# W5500.net
KiCad netlist of a schematic drawn in Altium Designer
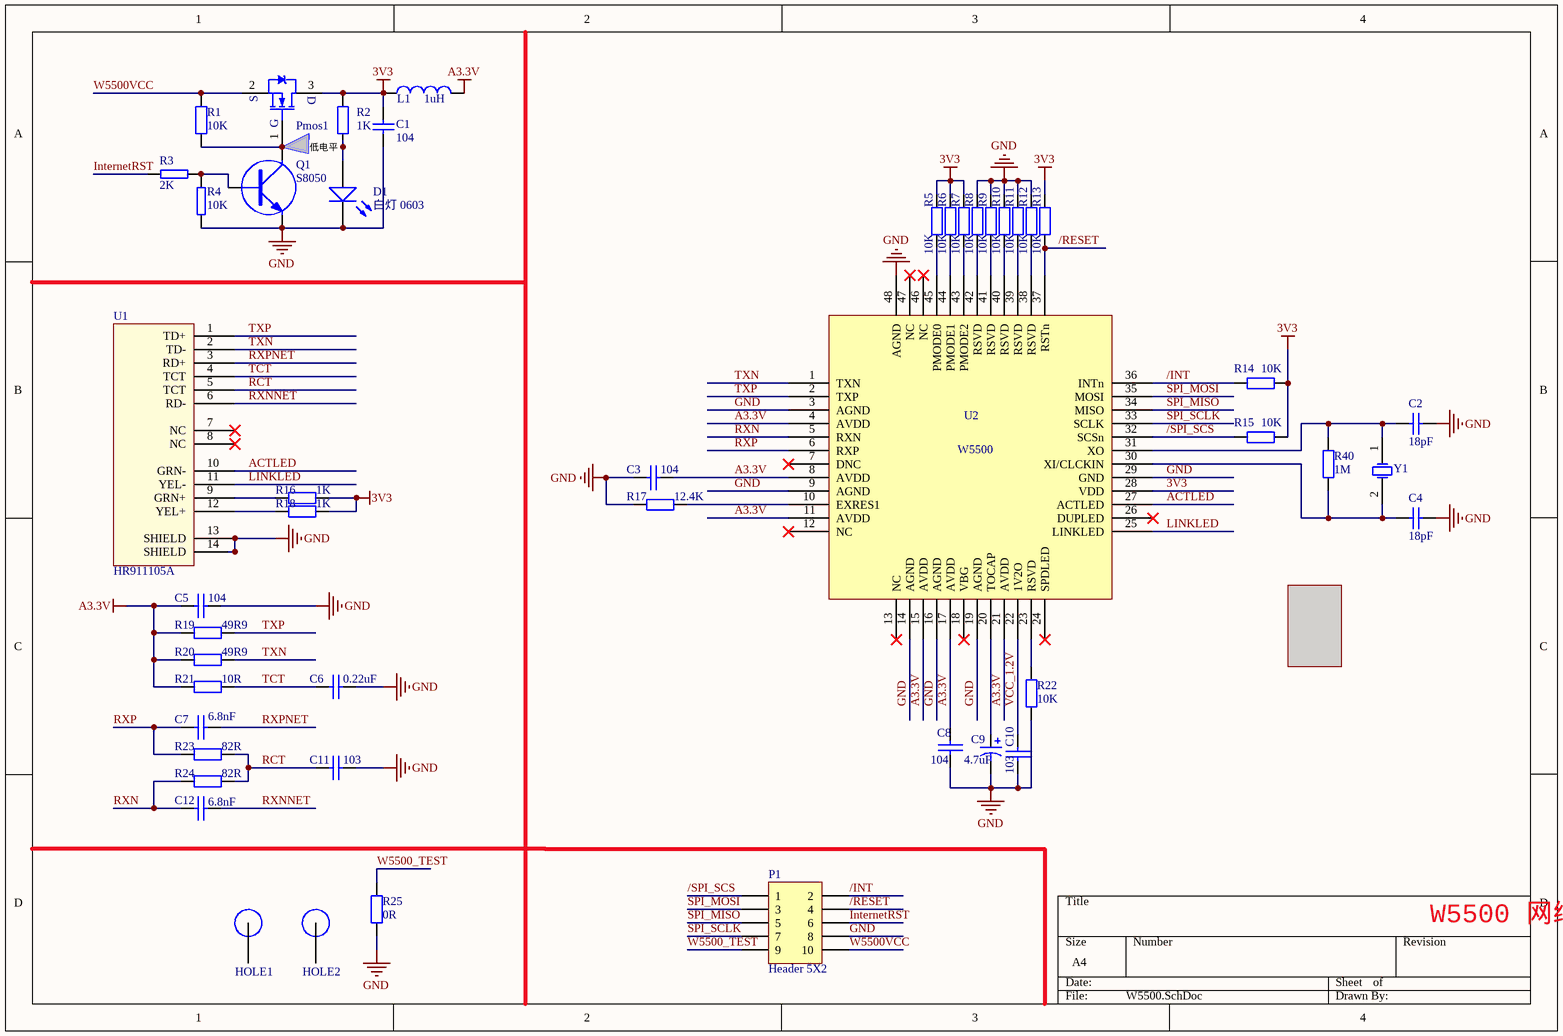
[diagram p0: W5500.SchDoc]

(export (version "E")
  (design (tool "Eeschema 10.0.6"))
  (components
    (comp (ref "C1")
      (value "104")
      (footprint "LC-0603_C")
      (description "Capacitor")
      (fields (field (name "PUBLISHER") "Altium Limited"))
      (libsource (lib "Miscellaneous Devices") (part "Cap"))
    )
    (comp (ref "C2")
      (value "18pF")
      (footprint "C0603")
      (description "Capacitor")
      (fields (field (name "PUBLISHER") "Altium Limited"))
      (libsource (lib "Miscellaneous Devices") (part "Cap"))
    )
    (comp (ref "C3")
      (value "104")
      (footprint "C0603")
      (description "Capacitor")
      (libsource (lib "*") (part "CAP"))
    )
    (comp (ref "C4")
      (value "18pF")
      (footprint "C0603")
      (description "Capacitor")
      (fields (field (name "PUBLISHER") "Altium Limited"))
      (libsource (lib "Miscellaneous Devices") (part "Cap"))
    )
    (comp (ref "C5")
      (value "104")
      (footprint "C0603")
      (description "Capacitor")
      (libsource (lib "*") (part "CAP"))
    )
    (comp (ref "C6")
      (value "0.22uF")
      (footprint "C0603")
      (description "Capacitor")
      (libsource (lib "*") (part "CAP"))
    )
    (comp (ref "C7")
      (value "6.8nF")
      (footprint "C0603")
      (description "Capacitor")
      (libsource (lib "*") (part "CAP"))
    )
    (comp (ref "C8")
      (value "104")
      (footprint "C0603")
      (description "Capacitor")
      (libsource (lib "*") (part "CAP"))
    )
    (comp (ref "C9")
      (value "4.7uF")
      (footprint "C0603")
      (description "Polarized Capacitor (Surface Mount)")
      (fields (field (name "PUBLISHER") "Altium Limited"))
      (libsource (lib "Miscellaneous Devices") (part "Cap Pol3"))
    )
    (comp (ref "C10")
      (value "103")
      (footprint "C0603")
      (description "Capacitor")
      (libsource (lib "*") (part "CAP"))
    )
    (comp (ref "C11")
      (value "103")
      (footprint "C0603")
      (description "Capacitor")
      (libsource (lib "*") (part "CAP"))
    )
    (comp (ref "C12")
      (value "6.8nF")
      (footprint "C0603")
      (description "Capacitor")
      (libsource (lib "*") (part "CAP"))
    )
    (comp (ref "D1")
      (value "白灯 0603")
      (footprint "LC-0603_LED_S1")
      (description "发光二极管")
      (libsource (lib "Miscellaneous Devices LC") (part "0603 白灯"))
    )
    (comp (ref "HOLE1") (value "HOLE") (footprint "H-3.2-3.2mm") (libsource (lib "接插件库") (part "HOLE")))
    (comp (ref "HOLE2") (value "HOLE") (footprint "H-3.2-3.2mm") (libsource (lib "接插件库") (part "HOLE")))
    (comp (ref "L1")
      (value "1uH")
      (footprint "LC-0805_L")
      (description "Inductor")
      (fields (field (name "PUBLISHER") "Altium Limited"))
      (libsource (lib "Miscellaneous Devices") (part "Inductor"))
    )
    (comp (ref "P1")
      (value "Header 5X2")
      (footprint "F2.54-2*5")
      (description "Header, 5-Pin, Dual row")
      (fields (field (name "PUBLISHER") "Altium Limited"))
      (libsource (lib "Miscellaneous Connectors") (part "Header 5X2"))
    )
    (comp (ref "Pmos1")
      (value "SI2301")
      (footprint "LC-SOT-23(SOT-23-3)")
      (libsource (lib "Sheet1 - 副本") (part "N-MOS"))
    )
    (comp (ref "Q1") (value "S8050") (footprint "LC-SOT-23(SOT-23-3)") (libsource (lib "*") (part "NPN")))
    (comp (ref "R1")
      (value "10K")
      (footprint "LC-0603_R")
      (description "Resistor")
      (fields (field (name "PUBLISHER") "Altium Limited"))
      (libsource (lib "") (part "Res2_2"))
    )
    (comp (ref "R2")
      (value "1K")
      (footprint "LC-0603_R")
      (description "Resistor")
      (fields (field (name "PUBLISHER") "Altium Limited"))
      (libsource (lib "") (part "Res2_2"))
    )
    (comp (ref "R3") (value "2K") (footprint "LC-0603_R") (libsource (lib "*") (part "RES")))
    (comp (ref "R4") (value "10K") (footprint "LC-0603_R") (libsource (lib "*") (part "RES")))
    (comp (ref "R5")
      (value "10K")
      (footprint "R0603")
      (description "Resistor")
      (fields (field (name "PUBLISHER") "Altium Limited"))
      (libsource (lib "Miscellaneous Devices") (part "Res2"))
    )
    (comp (ref "R6")
      (value "10K")
      (footprint "R0603")
      (description "Resistor")
      (fields (field (name "PUBLISHER") "Altium Limited"))
      (libsource (lib "Miscellaneous Devices") (part "Res2"))
    )
    (comp (ref "R7")
      (value "10K")
      (footprint "R0603")
      (description "Resistor")
      (fields (field (name "PUBLISHER") "Altium Limited"))
      (libsource (lib "Miscellaneous Devices") (part "Res2"))
    )
    (comp (ref "R8")
      (value "10K")
      (footprint "R0603")
      (description "Resistor")
      (fields (field (name "PUBLISHER") "Altium Limited"))
      (libsource (lib "Miscellaneous Devices") (part "Res2"))
    )
    (comp (ref "R9")
      (value "10K")
      (footprint "R0603")
      (description "Resistor")
      (fields (field (name "PUBLISHER") "Altium Limited"))
      (libsource (lib "Miscellaneous Devices") (part "Res2"))
    )
    (comp (ref "R10")
      (value "10K")
      (footprint "R0603")
      (description "Resistor")
      (fields (field (name "PUBLISHER") "Altium Limited"))
      (libsource (lib "Miscellaneous Devices") (part "Res2"))
    )
    (comp (ref "R11")
      (value "10K")
      (footprint "R0603")
      (description "Resistor")
      (fields (field (name "PUBLISHER") "Altium Limited"))
      (libsource (lib "Miscellaneous Devices") (part "Res2"))
    )
    (comp (ref "R12")
      (value "10K")
      (footprint "R0603")
      (description "Resistor")
      (fields (field (name "PUBLISHER") "Altium Limited"))
      (libsource (lib "Miscellaneous Devices") (part "Res2"))
    )
    (comp (ref "R13")
      (value "10K")
      (footprint "R0603")
      (description "Resistor")
      (fields (field (name "PUBLISHER") "Altium Limited"))
      (libsource (lib "Miscellaneous Devices") (part "Res2"))
    )
    (comp (ref "R14")
      (value "10K")
      (footprint "R0603")
      (description "Resistor")
      (fields (field (name "PUBLISHER") "Altium Limited"))
      (libsource (lib "") (part "Res2_3"))
    )
    (comp (ref "R15")
      (value "10K")
      (footprint "R0603")
      (description "Resistor")
      (fields (field (name "PUBLISHER") "Altium Limited"))
      (libsource (lib "") (part "Res2_3"))
    )
    (comp (ref "R16")
      (value "1K")
      (footprint "R0603")
      (description "Resistor")
      (fields (field (name "PUBLISHER") "Altium Limited"))
      (libsource (lib "") (part "Res2_1"))
    )
    (comp (ref "R17")
      (value "12.4K")
      (footprint "R0603")
      (description "Resistor")
      (fields (field (name "PUBLISHER") "Altium Limited"))
      (libsource (lib "") (part "Res2_3"))
    )
    (comp (ref "R18")
      (value "1K")
      (footprint "R0603")
      (description "Resistor")
      (fields (field (name "PUBLISHER") "Altium Limited"))
      (libsource (lib "") (part "Res2_1"))
    )
    (comp (ref "R19")
      (value "49R9")
      (footprint "R0603")
      (description "Resistor")
      (fields (field (name "PUBLISHER") "Altium Limited"))
      (libsource (lib "") (part "Res2_1"))
    )
    (comp (ref "R20")
      (value "49R9")
      (footprint "R0603")
      (description "Resistor")
      (fields (field (name "PUBLISHER") "Altium Limited"))
      (libsource (lib "") (part "Res2_1"))
    )
    (comp (ref "R21")
      (value "10R")
      (footprint "R0603")
      (description "Resistor")
      (fields (field (name "PUBLISHER") "Altium Limited"))
      (libsource (lib "") (part "Res2_1"))
    )
    (comp (ref "R22")
      (value "10K")
      (footprint "R0603")
      (description "Resistor")
      (fields (field (name "PUBLISHER") "Altium Limited"))
      (libsource (lib "Miscellaneous Devices") (part "Res2"))
    )
    (comp (ref "R23")
      (value "82R")
      (footprint "R0603")
      (description "Resistor")
      (fields (field (name "PUBLISHER") "Altium Limited"))
      (libsource (lib "") (part "Res2_1"))
    )
    (comp (ref "R24")
      (value "82R")
      (footprint "R0603")
      (description "Resistor")
      (fields (field (name "PUBLISHER") "Altium Limited"))
      (libsource (lib "") (part "Res2_1"))
    )
    (comp (ref "R25")
      (value "0R")
      (footprint "R0603")
      (description "Resistor")
      (fields (field (name "PUBLISHER") "Altium Limited"))
      (libsource (lib "") (part "Res2_2"))
    )
    (comp (ref "R40")
      (value "1M")
      (footprint "0603-1")
      (description "Resistor")
      (fields (field (name "PUBLISHER") "Altium Limited"))
      (libsource (lib "") (part "Res2_2"))
    )
    (comp (ref "U1") (value "HR911105A") (footprint "HR911105A") (libsource (lib "W5500") (part "HR911105A")))
    (comp (ref "U2")
      (value "W5500")
      (footprint "LQFP48")
      (description "W5500以太网芯片")
      (libsource (lib "W5500_SCH") (part "W5500"))
    )
    (comp (ref "Y1")
      (value "25MHz")
      (footprint "LC-SMD-5032_2P")
      (description "Crystal Oscillator")
      (fields (field (name "PUBLISHER") "Altium Limited"))
      (libsource (lib "Miscellaneous Devices") (part "XTAL"))
    )
  )
  (nets
    (net (code "1") (name "/ACTLED") (class "Default")
      (node (ref "U1") (pin "10") (pinfunction "GRN-_10") (pintype "passive"))
      (node (ref "U2") (pin "27") (pinfunction "ACTLED_27") (pintype "passive"))
    )
    (net (code "2") (name "/InternetRST") (class "Default")
      (node (ref "P1") (pin "6") (pinfunction "6_6") (pintype "passive"))
      (node (ref "R3") (pin "2") (pinfunction "2_2") (pintype "passive"))
    )
    (net (code "3") (name "/LINKLED") (class "Default")
      (node (ref "U1") (pin "11") (pinfunction "YEL-_11") (pintype "passive"))
      (node (ref "U2") (pin "25") (pinfunction "LINKLED_25") (pintype "passive"))
    )
    (net (code "4") (name "/RCT") (class "Default")
      (node (ref "C11") (pin "2") (pinfunction "2_2") (pintype "passive"))
      (node (ref "R23") (pin "2") (pinfunction "2_2") (pintype "passive"))
      (node (ref "R24") (pin "2") (pinfunction "2_2") (pintype "passive"))
      (node (ref "U1") (pin "5") (pinfunction "TCT_5") (pintype "passive"))
    )
    (net (code "5") (name "/RXN") (class "Default")
      (node (ref "C12") (pin "1") (pinfunction "1_1") (pintype "passive"))
      (node (ref "R24") (pin "1") (pinfunction "1_1") (pintype "passive"))
      (node (ref "U2") (pin "5") (pinfunction "RXN_5") (pintype "passive"))
    )
    (net (code "6") (name "/RXNNET") (class "Default")
      (node (ref "C12") (pin "2") (pinfunction "2_2") (pintype "passive"))
      (node (ref "U1") (pin "6") (pinfunction "RD-_6") (pintype "passive"))
    )
    (net (code "7") (name "/RXP") (class "Default")
      (node (ref "C7") (pin "1") (pinfunction "1_1") (pintype "passive"))
      (node (ref "R23") (pin "1") (pinfunction "1_1") (pintype "passive"))
      (node (ref "U2") (pin "6") (pinfunction "RXP_6") (pintype "passive"))
    )
    (net (code "8") (name "/RXPNET") (class "Default")
      (node (ref "C7") (pin "2") (pinfunction "2_2") (pintype "passive"))
      (node (ref "U1") (pin "3") (pinfunction "RD+_3") (pintype "passive"))
    )
    (net (code "9") (name "/SPI_MISO") (class "Default")
      (node (ref "P1") (pin "5") (pinfunction "5_5") (pintype "passive"))
      (node (ref "U2") (pin "34") (pinfunction "MISO_34") (pintype "passive"))
    )
    (net (code "10") (name "/SPI_MOSI") (class "Default")
      (node (ref "P1") (pin "3") (pinfunction "3_3") (pintype "passive"))
      (node (ref "U2") (pin "35") (pinfunction "MOSI_35") (pintype "passive"))
    )
    (net (code "11") (name "/SPI_SCLK") (class "Default")
      (node (ref "P1") (pin "7") (pinfunction "7_7") (pintype "passive"))
      (node (ref "U2") (pin "33") (pinfunction "SCLK_33") (pintype "passive"))
    )
    (net (code "12") (name "/TCT") (class "Default")
      (node (ref "C6") (pin "1") (pinfunction "1_1") (pintype "passive"))
      (node (ref "R21") (pin "2") (pinfunction "2_2") (pintype "passive"))
      (node (ref "U1") (pin "4") (pinfunction "TCT_4") (pintype "passive"))
    )
    (net (code "13") (name "/TXN") (class "Default")
      (node (ref "R20") (pin "2") (pinfunction "2_2") (pintype "passive"))
      (node (ref "U1") (pin "2") (pinfunction "TD-_2") (pintype "passive"))
      (node (ref "U2") (pin "1") (pinfunction "TXN_1") (pintype "passive"))
    )
    (net (code "14") (name "/TXP") (class "Default")
      (node (ref "R19") (pin "2") (pinfunction "2_2") (pintype "passive"))
      (node (ref "U1") (pin "1") (pinfunction "TD+_1") (pintype "passive"))
      (node (ref "U2") (pin "2") (pinfunction "TXP_2") (pintype "passive"))
    )
    (net (code "15") (name "/VCC_1.2V") (class "Default")
      (node (ref "C10") (pin "1") (pinfunction "1_1") (pintype "passive"))
      (node (ref "U2") (pin "22") (pinfunction "1V2O_22") (pintype "passive"))
    )
    (net (code "16") (name "/W5500VCC") (class "Default")
      (node (ref "P1") (pin "10") (pinfunction "10_10") (pintype "passive"))
      (node (ref "Pmos1") (pin "2") (pinfunction "S_2") (pintype "passive"))
      (node (ref "R1") (pin "2") (pinfunction "2_2") (pintype "passive"))
    )
    (net (code "17") (name "/W5500_TEST") (class "Default")
      (node (ref "P1") (pin "9") (pinfunction "9_9") (pintype "passive"))
      (node (ref "R25") (pin "2") (pinfunction "2_2") (pintype "passive"))
    )
    (net (code "18") (name "/{slash}INT") (class "Default")
      (node (ref "P1") (pin "2") (pinfunction "2_2") (pintype "passive"))
      (node (ref "R14") (pin "2") (pinfunction "2_2") (pintype "passive"))
      (node (ref "U2") (pin "36") (pinfunction "INTn_36") (pintype "passive"))
    )
    (net (code "19") (name "/{slash}RESET") (class "Default")
      (node (ref "P1") (pin "4") (pinfunction "4_4") (pintype "passive"))
      (node (ref "R13") (pin "2") (pinfunction "2_2") (pintype "passive"))
      (node (ref "U2") (pin "37") (pinfunction "RSTn_37") (pintype "passive"))
    )
    (net (code "20") (name "/{slash}SPI_SCS") (class "Default")
      (node (ref "P1") (pin "1") (pinfunction "1_1") (pintype "passive"))
      (node (ref "R15") (pin "2") (pinfunction "2_2") (pintype "passive"))
      (node (ref "U2") (pin "32") (pinfunction "SCSn_32") (pintype "passive"))
    )
    (net (code "21") (name "3V3") (class "Default")
      (node (ref "C1") (pin "2") (pinfunction "2_2") (pintype "passive"))
      (node (ref "L1") (pin "1") (pinfunction "1_1") (pintype "passive"))
      (node (ref "Pmos1") (pin "3") (pinfunction "D_3") (pintype "passive"))
      (node (ref "R13") (pin "1") (pinfunction "1_1") (pintype "passive"))
      (node (ref "R14") (pin "1") (pinfunction "1_1") (pintype "passive"))
      (node (ref "R15") (pin "1") (pinfunction "1_1") (pintype "passive"))
      (node (ref "R16") (pin "2") (pinfunction "2_2") (pintype "passive"))
      (node (ref "R18") (pin "2") (pinfunction "2_2") (pintype "passive"))
      (node (ref "R2") (pin "2") (pinfunction "2_2") (pintype "passive"))
      (node (ref "R5") (pin "1") (pinfunction "1_1") (pintype "passive"))
      (node (ref "R6") (pin "1") (pinfunction "1_1") (pintype "passive"))
      (node (ref "R7") (pin "1") (pinfunction "1_1") (pintype "passive"))
      (node (ref "U2") (pin "28") (pinfunction "VDD_28") (pintype "passive"))
    )
    (net (code "22") (name "A3.3V") (class "Default")
      (node (ref "C3") (pin "2") (pinfunction "2_2") (pintype "passive"))
      (node (ref "C5") (pin "2") (pinfunction "2_2") (pintype "passive"))
      (node (ref "C8") (pin "1") (pinfunction "1_1") (pintype "passive"))
      (node (ref "L1") (pin "2") (pinfunction "2_2") (pintype "passive"))
      (node (ref "R19") (pin "1") (pinfunction "1_1") (pintype "passive"))
      (node (ref "R20") (pin "1") (pinfunction "1_1") (pintype "passive"))
      (node (ref "R21") (pin "1") (pinfunction "1_1") (pintype "passive"))
      (node (ref "U2") (pin "11") (pinfunction "AVDD_11") (pintype "passive"))
      (node (ref "U2") (pin "15") (pinfunction "AVDD_15") (pintype "passive"))
      (node (ref "U2") (pin "17") (pinfunction "AVDD_17") (pintype "passive"))
      (node (ref "U2") (pin "21") (pinfunction "AVDD_21") (pintype "passive"))
      (node (ref "U2") (pin "4") (pinfunction "AVDD_4") (pintype "passive"))
      (node (ref "U2") (pin "8") (pinfunction "AVDD_8") (pintype "passive"))
    )
    (net (code "23") (name "GND") (class "Default")
      (node (ref "C1") (pin "1") (pinfunction "1_1") (pintype "passive"))
      (node (ref "C10") (pin "2") (pinfunction "2_2") (pintype "passive"))
      (node (ref "C11") (pin "1") (pinfunction "1_1") (pintype "passive"))
      (node (ref "C2") (pin "1") (pinfunction "1_1") (pintype "passive"))
      (node (ref "C3") (pin "1") (pinfunction "1_1") (pintype "passive"))
      (node (ref "C4") (pin "1") (pinfunction "1_1") (pintype "passive"))
      (node (ref "C5") (pin "1") (pinfunction "1_1") (pintype "passive"))
      (node (ref "C6") (pin "2") (pinfunction "2_2") (pintype "passive"))
      (node (ref "C8") (pin "2") (pinfunction "2_2") (pintype "passive"))
      (node (ref "C9") (pin "2") (pinfunction "2_2") (pintype "passive"))
      (node (ref "D1") (pin "K") (pinfunction "K_K") (pintype "passive"))
      (node (ref "P1") (pin "8") (pinfunction "8_8") (pintype "passive"))
      (node (ref "Q1") (pin "2") (pinfunction "2_2") (pintype "passive"))
      (node (ref "R10") (pin "1") (pinfunction "1_1") (pintype "passive"))
      (node (ref "R11") (pin "1") (pinfunction "1_1") (pintype "passive"))
      (node (ref "R12") (pin "1") (pinfunction "1_1") (pintype "passive"))
      (node (ref "R17") (pin "2") (pinfunction "2_2") (pintype "passive"))
      (node (ref "R22") (pin "2") (pinfunction "2_2") (pintype "passive"))
      (node (ref "R25") (pin "1") (pinfunction "1_1") (pintype "passive"))
      (node (ref "R4") (pin "1") (pinfunction "1_1") (pintype "passive"))
      (node (ref "R8") (pin "1") (pinfunction "1_1") (pintype "passive"))
      (node (ref "R9") (pin "1") (pinfunction "1_1") (pintype "passive"))
      (node (ref "U1") (pin "13") (pinfunction "SHIELD_13") (pintype "passive"))
      (node (ref "U1") (pin "14") (pinfunction "SHIELD_14") (pintype "passive"))
      (node (ref "U2") (pin "14") (pinfunction "AGND_14") (pintype "passive"))
      (node (ref "U2") (pin "16") (pinfunction "AGND_16") (pintype "passive"))
      (node (ref "U2") (pin "19") (pinfunction "AGND_19") (pintype "passive"))
      (node (ref "U2") (pin "29") (pinfunction "GND_29") (pintype "passive"))
      (node (ref "U2") (pin "3") (pinfunction "AGND_3") (pintype "passive"))
      (node (ref "U2") (pin "48") (pinfunction "AGND_48") (pintype "passive"))
      (node (ref "U2") (pin "9") (pinfunction "AGND_9") (pintype "passive"))
    )
    (net (code "24") (name "Net-(D1-PadA)") (class "Default")
      (node (ref "D1") (pin "A") (pinfunction "A_A") (pintype "passive"))
      (node (ref "R2") (pin "1") (pinfunction "1_1") (pintype "passive"))
    )
    (net (code "25") (name "Net-(Pmos1-G)") (class "Default")
      (node (ref "Pmos1") (pin "1") (pinfunction "G_1") (pintype "passive"))
      (node (ref "Q1") (pin "3") (pinfunction "3_3") (pintype "passive"))
      (node (ref "R1") (pin "1") (pinfunction "1_1") (pintype "passive"))
    )
    (net (code "26") (name "Net-(Q1-Pad1)") (class "Default")
      (node (ref "Q1") (pin "1") (pinfunction "1_1") (pintype "passive"))
      (node (ref "R3") (pin "1") (pinfunction "1_1") (pintype "passive"))
      (node (ref "R4") (pin "2") (pinfunction "2_2") (pintype "passive"))
    )
    (net (code "27") (name "Net-(R8-Pad2)") (class "Default")
      (node (ref "R8") (pin "2") (pinfunction "2_2") (pintype "passive"))
      (node (ref "U2") (pin "42") (pinfunction "RSVD_42") (pintype "passive"))
    )
    (net (code "28") (name "Net-(R9-Pad2)") (class "Default")
      (node (ref "R9") (pin "2") (pinfunction "2_2") (pintype "passive"))
      (node (ref "U2") (pin "41") (pinfunction "RSVD_41") (pintype "passive"))
    )
    (net (code "29") (name "Net-(R10-Pad2)") (class "Default")
      (node (ref "R10") (pin "2") (pinfunction "2_2") (pintype "passive"))
      (node (ref "U2") (pin "40") (pinfunction "RSVD_40") (pintype "passive"))
    )
    (net (code "30") (name "Net-(R11-Pad2)") (class "Default")
      (node (ref "R11") (pin "2") (pinfunction "2_2") (pintype "passive"))
      (node (ref "U2") (pin "39") (pinfunction "RSVD_39") (pintype "passive"))
    )
    (net (code "31") (name "Net-(R12-Pad2)") (class "Default")
      (node (ref "R12") (pin "2") (pinfunction "2_2") (pintype "passive"))
      (node (ref "U2") (pin "38") (pinfunction "RSVD_38") (pintype "passive"))
    )
    (net (code "32") (name "Net-(R22-Pad1)") (class "Default")
      (node (ref "R22") (pin "1") (pinfunction "1_1") (pintype "passive"))
      (node (ref "U2") (pin "23") (pinfunction "RSVD_23") (pintype "passive"))
    )
    (net (code "33") (name "Net-(U1-GRN+)") (class "Default")
      (node (ref "R16") (pin "1") (pinfunction "1_1") (pintype "passive"))
      (node (ref "U1") (pin "9") (pinfunction "GRN+_9") (pintype "passive"))
    )
    (net (code "34") (name "Net-(U1-YEL+)") (class "Default")
      (node (ref "R18") (pin "1") (pinfunction "1_1") (pintype "passive"))
      (node (ref "U1") (pin "12") (pinfunction "YEL+_12") (pintype "passive"))
    )
    (net (code "35") (name "Net-(U2-EXRES1)") (class "Default")
      (node (ref "R17") (pin "1") (pinfunction "1_1") (pintype "passive"))
      (node (ref "U2") (pin "10") (pinfunction "EXRES1_10") (pintype "passive"))
    )
    (net (code "36") (name "Net-(U2-PMODE0)") (class "Default")
      (node (ref "R5") (pin "2") (pinfunction "2_2") (pintype "passive"))
      (node (ref "U2") (pin "45") (pinfunction "PMODE0_45") (pintype "passive"))
    )
    (net (code "37") (name "Net-(U2-PMODE1)") (class "Default")
      (node (ref "R6") (pin "2") (pinfunction "2_2") (pintype "passive"))
      (node (ref "U2") (pin "44") (pinfunction "PMODE1_44") (pintype "passive"))
    )
    (net (code "38") (name "Net-(U2-PMODE2)") (class "Default")
      (node (ref "R7") (pin "2") (pinfunction "2_2") (pintype "passive"))
      (node (ref "U2") (pin "43") (pinfunction "PMODE2_43") (pintype "passive"))
    )
    (net (code "39") (name "Net-(U2-TOCAP)") (class "Default")
      (node (ref "C9") (pin "1") (pinfunction "1_1") (pintype "passive"))
      (node (ref "U2") (pin "20") (pinfunction "TOCAP_20") (pintype "passive"))
    )
    (net (code "40") (name "Net-(U2-XI{slash}CLCKIN)") (class "Default")
      (node (ref "C4") (pin "2") (pinfunction "2_2") (pintype "passive"))
      (node (ref "R40") (pin "1") (pinfunction "1_1") (pintype "passive"))
      (node (ref "U2") (pin "30") (pinfunction "XI/CLCKIN_30") (pintype "passive"))
      (node (ref "Y1") (pin "2") (pinfunction "OSC2_2") (pintype "passive"))
    )
    (net (code "41") (name "Net-(U2-XO)") (class "Default")
      (node (ref "C2") (pin "2") (pinfunction "2_2") (pintype "passive"))
      (node (ref "R40") (pin "2") (pinfunction "2_2") (pintype "passive"))
      (node (ref "U2") (pin "31") (pinfunction "XO_31") (pintype "passive"))
      (node (ref "Y1") (pin "1") (pinfunction "OSC1_1") (pintype "passive"))
    )
    (net (code "42") (name "unconnected-(HOLE1-Pad1)") (class "Default")
      (node (ref "HOLE1") (pin "1") (pinfunction "1_1") (pintype "passive"))
    )
    (net (code "43") (name "unconnected-(HOLE2-Pad1)") (class "Default")
      (node (ref "HOLE2") (pin "1") (pinfunction "1_1") (pintype "passive"))
    )
    (net (code "44") (name "unconnected-(U1-NC-Pad7)") (class "Default")
      (node (ref "U1") (pin "7") (pinfunction "NC_7") (pintype "passive+no_connect"))
    )
    (net (code "45") (name "unconnected-(U1-NC-Pad8)") (class "Default")
      (node (ref "U1") (pin "8") (pinfunction "NC_8") (pintype "passive+no_connect"))
    )
    (net (code "46") (name "unconnected-(U2-DNC-Pad7)") (class "Default")
      (node (ref "U2") (pin "7") (pinfunction "DNC_7") (pintype "passive+no_connect"))
    )
    (net (code "47") (name "unconnected-(U2-DUPLED-Pad26)") (class "Default")
      (node (ref "U2") (pin "26") (pinfunction "DUPLED_26") (pintype "passive+no_connect"))
    )
    (net (code "48") (name "unconnected-(U2-NC-Pad12)") (class "Default")
      (node (ref "U2") (pin "12") (pinfunction "NC_12") (pintype "passive+no_connect"))
    )
    (net (code "49") (name "unconnected-(U2-NC-Pad13)") (class "Default")
      (node (ref "U2") (pin "13") (pinfunction "NC_13") (pintype "passive+no_connect"))
    )
    (net (code "50") (name "unconnected-(U2-NC-Pad46)") (class "Default")
      (node (ref "U2") (pin "46") (pinfunction "NC_46") (pintype "passive+no_connect"))
    )
    (net (code "51") (name "unconnected-(U2-NC-Pad47)") (class "Default")
      (node (ref "U2") (pin "47") (pinfunction "NC_47") (pintype "passive+no_connect"))
    )
    (net (code "52") (name "unconnected-(U2-SPDLED-Pad24)") (class "Default")
      (node (ref "U2") (pin "24") (pinfunction "SPDLED_24") (pintype "passive+no_connect"))
    )
    (net (code "53") (name "unconnected-(U2-VBG-Pad18)") (class "Default")
      (node (ref "U2") (pin "18") (pinfunction "VBG_18") (pintype "passive+no_connect"))
    )
  )
)
